# joint_board_boosterpack_motor_drivers.net
KiCad netlist of a schematic drawn in Altium Designer
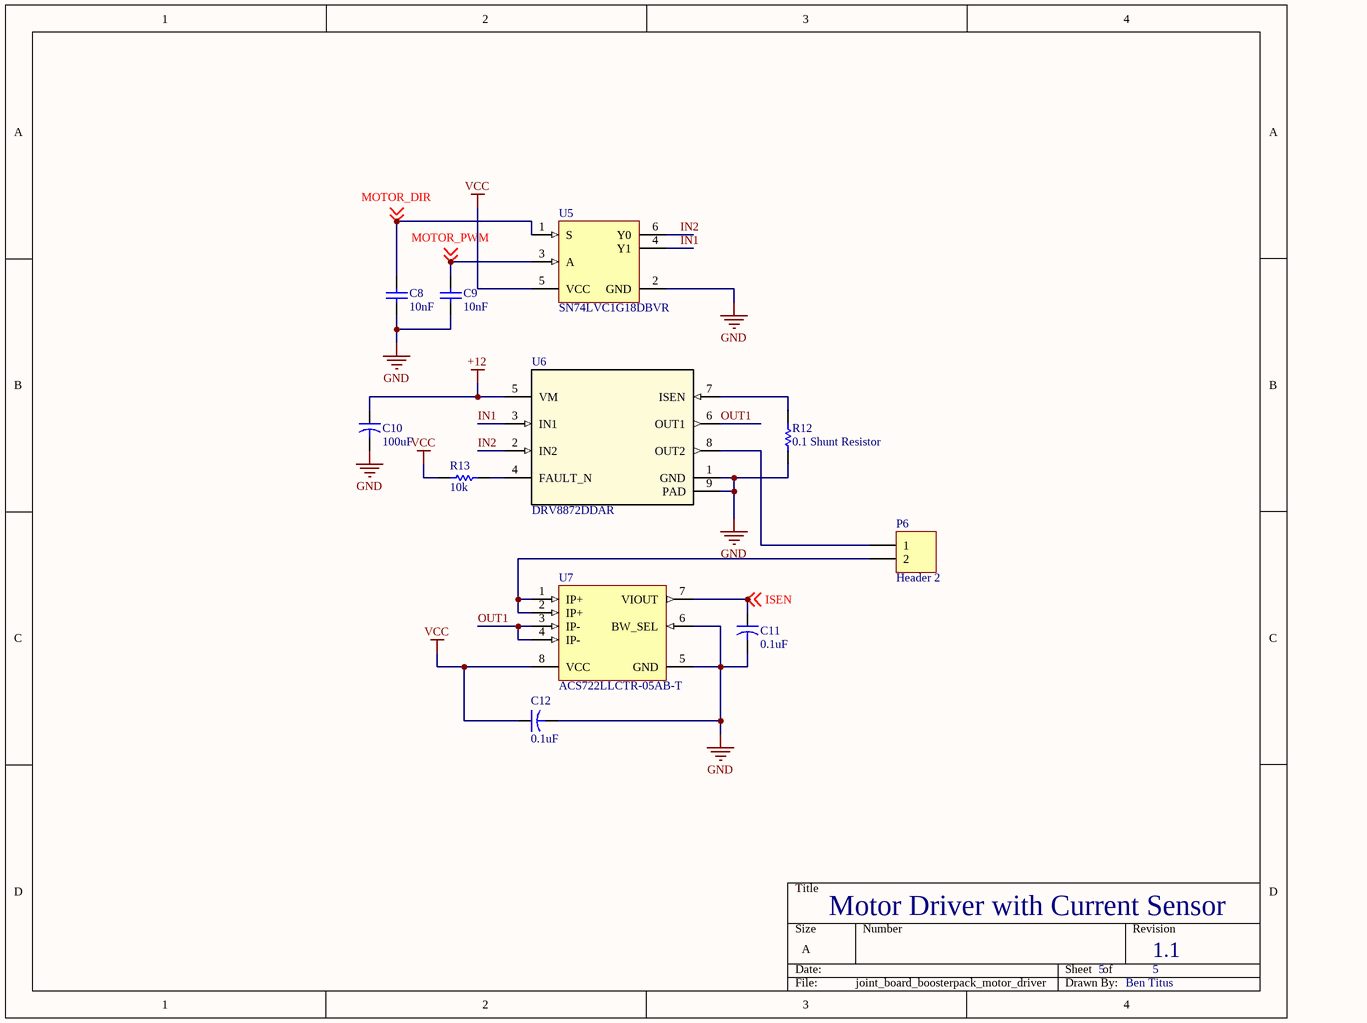
[diagram p0: joint_board_boosterpack_motor_drivers.SchDoc]

(export (version "E")
  (design (tool "Eeschema 10.0.6"))
  (components
    (comp (ref "C8")
      (value "10nF")
      (footprint "CAPC0805(2012)145_L")
      (description "0805 (2012 Metric) Chip Capacitor")
      (libsource (lib "Altium Content Vault") (part "CAP_5"))
    )
    (comp (ref "C9")
      (value "10nF")
      (footprint "CAPC0805(2012)145_L")
      (description "0805 (2012 Metric) Chip Capacitor")
      (libsource (lib "Altium Content Vault") (part "CAP_5"))
    )
    (comp (ref "C10")
      (value "100uF")
      (footprint "CAPR5-4X5")
      (description "100uF Filter Capacitor")
      (fields (field (name "PUBLISHER") "Altium Limited"))
      (libsource (lib "Miscellaneous Devices") (part "Cap2"))
    )
    (comp (ref "C11")
      (value "0.1uF")
      (footprint "CAPR5-4X5")
      (description "Capacitor")
      (fields (field (name "PUBLISHER") "Altium Limited"))
      (libsource (lib "Miscellaneous Devices") (part "Cap2"))
    )
    (comp (ref "C12")
      (value "0.1uF")
      (footprint "CAPR5-4X5")
      (description "Capacitor")
      (fields (field (name "PUBLISHER") "Altium Limited"))
      (libsource (lib "Miscellaneous Devices") (part "Cap2"))
    )
    (comp (ref "P6")
      (value "Header 2")
      (footprint "HDR1X2")
      (description "Header, 2-Pin")
      (fields (field (name "PUBLISHER") "Altium Limited"))
      (libsource (lib "Miscellaneous Connectors") (part "Header 2"))
    )
    (comp (ref "R12")
      (value "0.1 Shunt Resistor")
      (footprint "RESC2512(6432)_L")
      (description "2512 (6432 Metric) Chip Resistor")
      (libsource (lib "Altium Content Vault") (part "RES_3"))
    )
    (comp (ref "R13")
      (value "10k")
      (footprint "RESC0805(2012)_L")
      (description "0805 (2012 Metric) Chip Resistor")
      (libsource (lib "Altium Content Vault") (part "RES_3"))
    )
    (comp (ref "U5")
      (value "SN74LVC1G18DBVR")
      (footprint "DBV0006A_L")
      (description "One of Two Noninverting Demultiplexer with 3-State Deselected Output, DBV0006A, LARGE T&R")
      (fields
        (field (name "MANUFACTURER") "Texas Instruments")
        (field (name "GENERIC PART NUMBER") "SN74LVC1G18")
      )
      (libsource (lib "Altium Content Vault") (part "TI-SN74LVC1G18-6"))
    )
    (comp (ref "U6")
      (value "DRV8872DDAR")
      (footprint "DDA0008H_N")
      (description "Imported")
      (fields
        (field (name "ALTERNATE_PARTNUMBER") "DRV8872DDA")
        (field (name "MANUFACTURER") "Texas Instruments")
      )
      (libsource (lib "Custom_Lib") (part "DRV8872DDAR"))
    )
    (comp (ref "U7")
      (value "ACS722LLCTR-05AB-T")
      (footprint "ALEG-LC-8_V")
      (libsource (lib "Altium Content Vault") (part "ALEG-ACS722-SOIC-8"))
    )
  )
  (nets
    (net (code "1") (name "+12") (class "Default")
      (node (ref "C10") (pin "1") (pinfunction "1_1") (pintype "passive"))
      (node (ref "U6") (pin "5") (pinfunction "VM_5") (pintype "power_in"))
    )
    (net (code "2") (name "/IN1") (class "Default")
      (node (ref "U5") (pin "4") (pinfunction "Y1_4") (pintype "tri_state"))
      (node (ref "U6") (pin "3") (pinfunction "IN1_3") (pintype "input"))
    )
    (net (code "3") (name "/IN2") (class "Default")
      (node (ref "U5") (pin "6") (pinfunction "Y0_6") (pintype "tri_state"))
      (node (ref "U6") (pin "2") (pinfunction "IN2_2") (pintype "input"))
    )
    (net (code "4") (name "/OUT1") (class "Default")
      (node (ref "U6") (pin "6") (pinfunction "OUT1_6") (pintype "output"))
      (node (ref "U7") (pin "3") (pinfunction "IP-_3") (pintype "input"))
      (node (ref "U7") (pin "4") (pinfunction "IP-_4") (pintype "input"))
    )
    (net (code "5") (name "GND") (class "Default")
      (node (ref "C10") (pin "2") (pinfunction "2_2") (pintype "passive"))
      (node (ref "C11") (pin "2") (pinfunction "2_2") (pintype "passive"))
      (node (ref "C12") (pin "2") (pinfunction "2_2") (pintype "passive"))
      (node (ref "C8") (pin "1") (pinfunction "1_1") (pintype "passive"))
      (node (ref "C9") (pin "1") (pinfunction "1_1") (pintype "passive"))
      (node (ref "R12") (pin "1") (pinfunction "1_1") (pintype "passive"))
      (node (ref "U5") (pin "2") (pinfunction "GND_2") (pintype "power_in"))
      (node (ref "U6") (pin "1") (pinfunction "GND_1") (pintype "power_in"))
      (node (ref "U6") (pin "9") (pinfunction "PAD_9") (pintype "power_in"))
      (node (ref "U7") (pin "5") (pinfunction "GND_5") (pintype "power_in"))
      (node (ref "U7") (pin "6") (pinfunction "BW_SEL_6") (pintype "input"))
    )
    (net (code "6") (name "ISEN") (class "Default")
      (node (ref "C11") (pin "1") (pinfunction "1_1") (pintype "passive"))
      (node (ref "U7") (pin "7") (pinfunction "VIOUT_7") (pintype "output"))
    )
    (net (code "7") (name "MOTOR_DIR") (class "Default")
      (node (ref "C8") (pin "2") (pinfunction "2_2") (pintype "passive"))
      (node (ref "U5") (pin "1") (pinfunction "S_1") (pintype "input"))
    )
    (net (code "8") (name "MOTOR_PWM") (class "Default")
      (node (ref "C9") (pin "2") (pinfunction "2_2") (pintype "passive"))
      (node (ref "U5") (pin "3") (pinfunction "A_3") (pintype "input"))
    )
    (net (code "9") (name "Net-(P6-Pad2)") (class "Default")
      (node (ref "P6") (pin "2") (pinfunction "2_2") (pintype "passive"))
      (node (ref "U7") (pin "1") (pinfunction "IP+_1") (pintype "input"))
      (node (ref "U7") (pin "2") (pinfunction "IP+_2") (pintype "input"))
    )
    (net (code "10") (name "Net-(U6-FAULT_N)") (class "Default")
      (node (ref "R13") (pin "2") (pinfunction "2_2") (pintype "passive"))
      (node (ref "U6") (pin "4") (pinfunction "FAULT_N_4") (pintype "open_collector"))
    )
    (net (code "11") (name "Net-(U6-ISEN)") (class "Default")
      (node (ref "R12") (pin "2") (pinfunction "2_2") (pintype "passive"))
      (node (ref "U6") (pin "7") (pinfunction "ISEN_7") (pintype "input"))
    )
    (net (code "12") (name "Net-(U6-OUT2)") (class "Default")
      (node (ref "P6") (pin "1") (pinfunction "1_1") (pintype "passive"))
      (node (ref "U6") (pin "8") (pinfunction "OUT2_8") (pintype "output"))
    )
    (net (code "13") (name "VCC") (class "Default")
      (node (ref "C12") (pin "1") (pinfunction "1_1") (pintype "passive"))
      (node (ref "R13") (pin "1") (pinfunction "1_1") (pintype "passive"))
      (node (ref "U5") (pin "5") (pinfunction "VCC_5") (pintype "power_in"))
      (node (ref "U7") (pin "8") (pinfunction "VCC_8") (pintype "power_in"))
    )
  )
)
